# RTDPlug.net
KiCad netlist of a schematic drawn in EAGLE
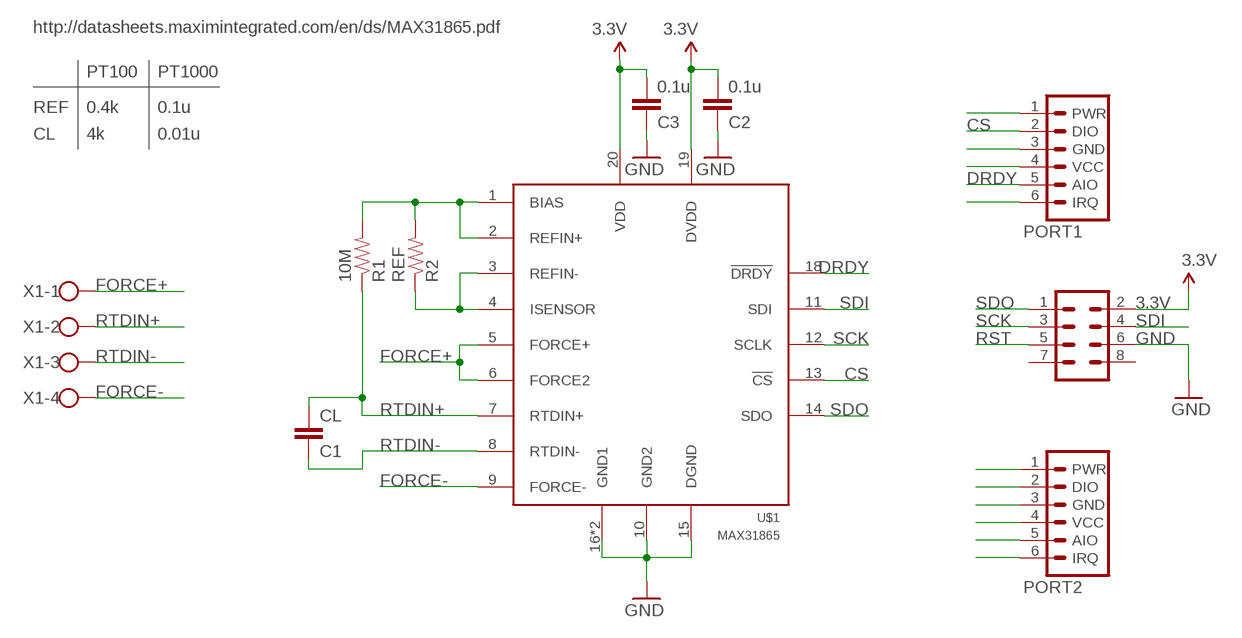
[diagram p0: schematic, sheet 1]

(export (version "E")
  (design (tool "Eeschema 10.0.6"))
  (components
    (comp (ref "C1")
      (value "CL")
      (footprint "eagle-import:0603-CAP")
      (libsource (lib "eagle-import") (part "CAP0603-CAP"))
    )
    (comp (ref "C2")
      (value "0.1u")
      (footprint "eagle-import:0603-CAP")
      (libsource (lib "eagle-import") (part "CAP0603-CAP"))
    )
    (comp (ref "C3")
      (value "0.1u")
      (footprint "eagle-import:0603-CAP")
      (libsource (lib "eagle-import") (part "CAP0603-CAP"))
    )
    (comp (ref "ISP")
      (value "MA04-2")
      (footprint "eagle-import:MA04-2")
      (libsource (lib "eagle-import") (part "MA04-2"))
    )
    (comp (ref "PORT1")
      (value "JEEPORT-FEMALE")
      (footprint "eagle-import:1X06_FEMALE_LOCK.010")
      (libsource (lib "eagle-import") (part "JEEPORT-FEMALE"))
    )
    (comp (ref "PORT2")
      (value "JEEPORT-FEMALE")
      (footprint "eagle-import:1X06_FEMALE_LOCK.010")
      (libsource (lib "eagle-import") (part "JEEPORT-FEMALE"))
    )
    (comp (ref "R1")
      (value "10M")
      (footprint "eagle-import:0603-RES")
      (libsource (lib "eagle-import") (part "RESISTOR0603-RES"))
    )
    (comp (ref "R2")
      (value "REF")
      (footprint "eagle-import:1206")
      (libsource (lib "eagle-import") (part "RESISTOR1206"))
    )
    (comp (ref "U$1")
      (value "MAX31865")
      (footprint "eagle-import:TQFN20-5X5")
      (libsource (lib "eagle-import") (part "MAX31865"))
    )
    (comp (ref "X1")
      (value "W237-4")
      (footprint "eagle-import:W237-4")
      (libsource (lib "eagle-import") (part "W237-4"))
    )
  )
  (nets
    (net (code "1") (name "/CS") (class "Default")
      (node (ref "PORT1") (pin "2") (pinfunction "DIO_2") (pintype "bidirectional"))
      (node (ref "U$1") (pin "13") (pinfunction "~{CS}_13") (pintype "input"))
    )
    (net (code "2") (name "/DRDY") (class "Default")
      (node (ref "PORT1") (pin "5") (pinfunction "AIO_5") (pintype "bidirectional"))
      (node (ref "U$1") (pin "18") (pinfunction "~{DRDY}_18") (pintype "output"))
    )
    (net (code "3") (name "/FORCE+") (class "Default")
      (node (ref "U$1") (pin "5") (pinfunction "FORCE+_5") (pintype "input"))
      (node (ref "U$1") (pin "6") (pinfunction "FORCE2_6") (pintype "input"))
      (node (ref "X1") (pin "1") (pinfunction "KL_1") (pintype "passive"))
    )
    (net (code "4") (name "/FORCE-") (class "Default")
      (node (ref "U$1") (pin "9") (pinfunction "FORCE-_9") (pintype "input"))
      (node (ref "X1") (pin "4") (pinfunction "KL_4") (pintype "passive"))
    )
    (net (code "5") (name "/RST") (class "Default")
      (node (ref "ISP") (pin "5") (pinfunction "5_5") (pintype "passive"))
    )
    (net (code "6") (name "/RTDIN+") (class "Default")
      (node (ref "C1") (pin "2") (pinfunction "2_2") (pintype "passive"))
      (node (ref "R1") (pin "1") (pinfunction "1_1") (pintype "passive"))
      (node (ref "U$1") (pin "7") (pinfunction "RTDIN+_7") (pintype "input"))
      (node (ref "X1") (pin "2") (pinfunction "KL_2") (pintype "passive"))
    )
    (net (code "7") (name "/RTDIN-") (class "Default")
      (node (ref "C1") (pin "1") (pinfunction "1_1") (pintype "passive"))
      (node (ref "U$1") (pin "8") (pinfunction "RTDIN-_8") (pintype "input"))
      (node (ref "X1") (pin "3") (pinfunction "KL_3") (pintype "passive"))
    )
    (net (code "8") (name "/SCK") (class "Default")
      (node (ref "ISP") (pin "3") (pinfunction "3_3") (pintype "passive"))
      (node (ref "U$1") (pin "12") (pinfunction "SCLK_12") (pintype "input"))
    )
    (net (code "9") (name "/SDI") (class "Default")
      (node (ref "ISP") (pin "4") (pinfunction "4_4") (pintype "passive"))
      (node (ref "U$1") (pin "11") (pinfunction "SDI_11") (pintype "input"))
    )
    (net (code "10") (name "/SDO") (class "Default")
      (node (ref "ISP") (pin "1") (pinfunction "1_1") (pintype "passive"))
      (node (ref "U$1") (pin "14") (pinfunction "SDO_14") (pintype "output"))
    )
    (net (code "11") (name "3.3V") (class "Default")
      (node (ref "C2") (pin "2") (pinfunction "2_2") (pintype "passive"))
      (node (ref "C3") (pin "2") (pinfunction "2_2") (pintype "passive"))
      (node (ref "ISP") (pin "2") (pinfunction "2_2") (pintype "passive"))
      (node (ref "U$1") (pin "19") (pinfunction "DVDD_19") (pintype "power_in"))
      (node (ref "U$1") (pin "20") (pinfunction "VDD_20") (pintype "power_in"))
    )
    (net (code "12") (name "GND") (class "Default")
      (node (ref "C2") (pin "1") (pinfunction "1_1") (pintype "passive"))
      (node (ref "C3") (pin "1") (pinfunction "1_1") (pintype "passive"))
      (node (ref "ISP") (pin "6") (pinfunction "6_6") (pintype "passive"))
      (node (ref "U$1") (pin "10") (pinfunction "GND2_10") (pintype "power_in"))
      (node (ref "U$1") (pin "15") (pinfunction "DGND_15") (pintype "power_in"))
      (node (ref "U$1") (pin "16") (pinfunction "GND1_16") (pintype "power_in"))
      (node (ref "U$1") (pin "EXP") (pinfunction "GND1_EXP") (pintype "power_in"))
    )
    (net (code "13") (name "Net-(U$1-BIAS)") (class "Default")
      (node (ref "R1") (pin "2") (pinfunction "2_2") (pintype "passive"))
      (node (ref "R2") (pin "2") (pinfunction "2_2") (pintype "passive"))
      (node (ref "U$1") (pin "1") (pinfunction "BIAS_1") (pintype "input"))
      (node (ref "U$1") (pin "2") (pinfunction "REFIN+_2") (pintype "input"))
    )
    (net (code "14") (name "Net-(U$1-ISENSOR)") (class "Default")
      (node (ref "R2") (pin "1") (pinfunction "1_1") (pintype "passive"))
      (node (ref "U$1") (pin "3") (pinfunction "REFIN-_3") (pintype "input"))
      (node (ref "U$1") (pin "4") (pinfunction "ISENSOR_4") (pintype "input"))
    )
    (net (code "15") (name "unconnected-(ISP-Pad7)") (class "Default")
      (node (ref "ISP") (pin "7") (pinfunction "7_7") (pintype "passive"))
    )
    (net (code "16") (name "unconnected-(ISP-Pad8)") (class "Default")
      (node (ref "ISP") (pin "8") (pinfunction "8_8") (pintype "passive"))
    )
    (net (code "17") (name "unconnected-(PORT1-GND-Pad3)") (class "Default")
      (node (ref "PORT1") (pin "3") (pinfunction "GND_3") (pintype "power_in"))
    )
    (net (code "18") (name "unconnected-(PORT1-IRQ-Pad6)") (class "Default")
      (node (ref "PORT1") (pin "6") (pinfunction "IRQ_6") (pintype "bidirectional"))
    )
    (net (code "19") (name "unconnected-(PORT1-PWR-Pad1)") (class "Default")
      (node (ref "PORT1") (pin "1") (pinfunction "PWR_1") (pintype "power_in"))
    )
    (net (code "20") (name "unconnected-(PORT1-VCC-Pad4)") (class "Default")
      (node (ref "PORT1") (pin "4") (pinfunction "VCC_4") (pintype "power_in"))
    )
    (net (code "21") (name "unconnected-(PORT2-AIO-Pad5)") (class "Default")
      (node (ref "PORT2") (pin "5") (pinfunction "AIO_5") (pintype "bidirectional"))
    )
    (net (code "22") (name "unconnected-(PORT2-DIO-Pad2)") (class "Default")
      (node (ref "PORT2") (pin "2") (pinfunction "DIO_2") (pintype "bidirectional"))
    )
    (net (code "23") (name "unconnected-(PORT2-GND-Pad3)") (class "Default")
      (node (ref "PORT2") (pin "3") (pinfunction "GND_3") (pintype "power_in"))
    )
    (net (code "24") (name "unconnected-(PORT2-IRQ-Pad6)") (class "Default")
      (node (ref "PORT2") (pin "6") (pinfunction "IRQ_6") (pintype "bidirectional"))
    )
    (net (code "25") (name "unconnected-(PORT2-PWR-Pad1)") (class "Default")
      (node (ref "PORT2") (pin "1") (pinfunction "PWR_1") (pintype "power_in"))
    )
    (net (code "26") (name "unconnected-(PORT2-VCC-Pad4)") (class "Default")
      (node (ref "PORT2") (pin "4") (pinfunction "VCC_4") (pintype "power_in"))
    )
  )
)
